# untitled.net
KiCad netlist of a schematic drawn in EAGLE
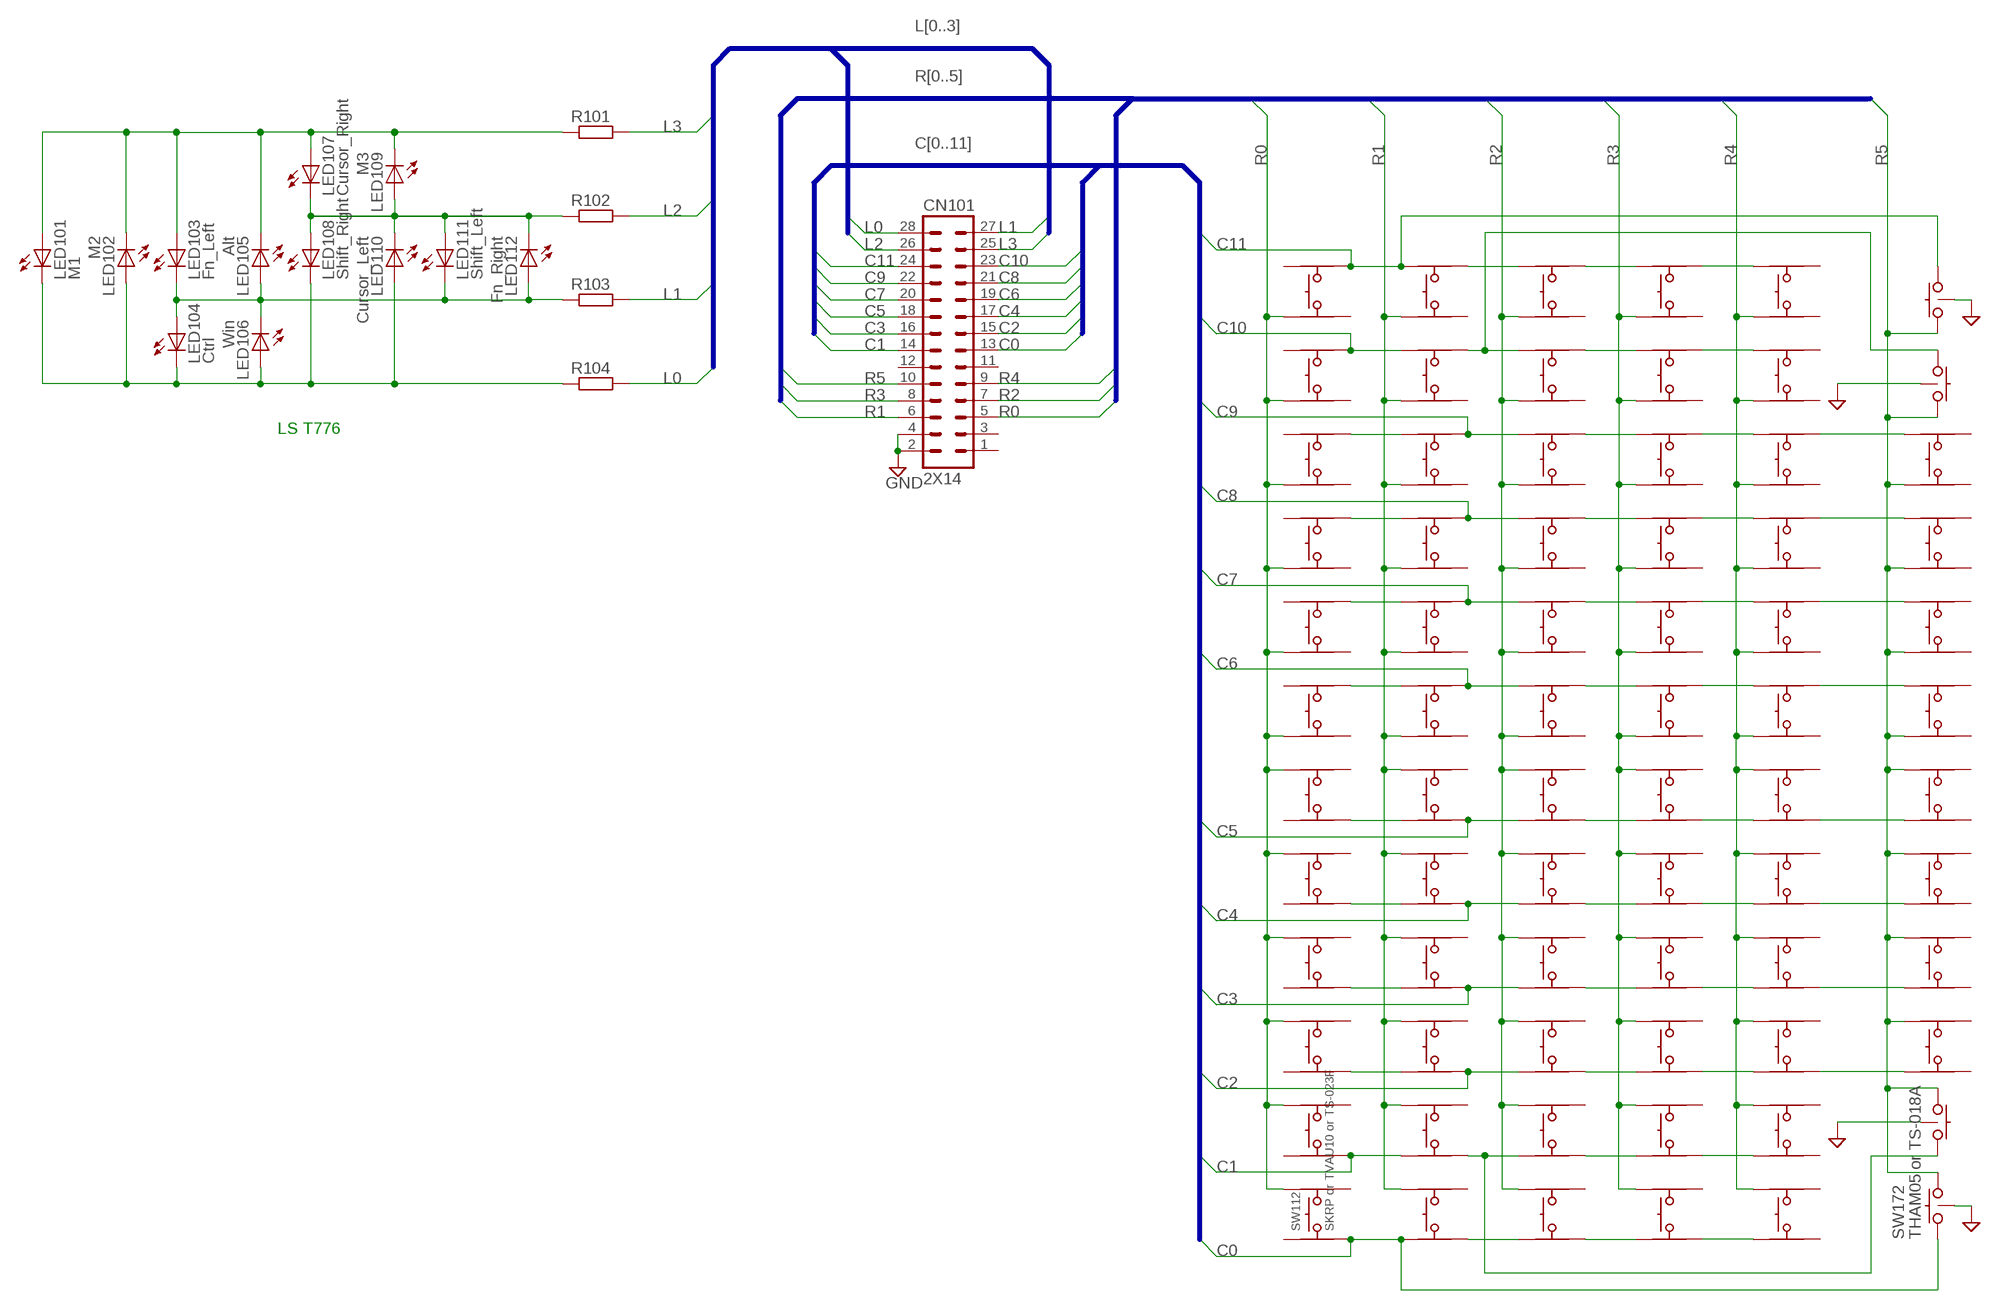
[diagram p0: schematic, sheet 1]

(export (version "E")
  (design (tool "Eeschema 10.0.6"))
  (components
    (comp (ref "CN101")
      (value "2X14")
      (footprint "eagle-import:2MM_14X2")
      (libsource (lib "eagle-import") (part "2X14"))
    )
    (comp (ref "LED101")
      (value "M1")
      (footprint "eagle-import:P-LCC-2-TOPLED-RG")
      (libsource (lib "eagle-import") (part "LEDP-LCC-2-BACK"))
    )
    (comp (ref "LED102")
      (value "M2")
      (footprint "eagle-import:P-LCC-2-TOPLED-RG")
      (libsource (lib "eagle-import") (part "LEDP-LCC-2-BACK"))
    )
    (comp (ref "LED103")
      (value "Fn_Left")
      (footprint "eagle-import:P-LCC-2-TOPLED-RG")
      (libsource (lib "eagle-import") (part "LEDP-LCC-2-BACK"))
    )
    (comp (ref "LED104")
      (value "Ctrl")
      (footprint "eagle-import:P-LCC-2-TOPLED-RG")
      (libsource (lib "eagle-import") (part "LEDP-LCC-2-BACK"))
    )
    (comp (ref "LED105")
      (value "Alt")
      (footprint "eagle-import:P-LCC-2-TOPLED-RG")
      (libsource (lib "eagle-import") (part "LEDP-LCC-2-BACK"))
    )
    (comp (ref "LED106")
      (value "Win")
      (footprint "eagle-import:P-LCC-2-TOPLED-RG")
      (libsource (lib "eagle-import") (part "LEDP-LCC-2-BACK"))
    )
    (comp (ref "LED107")
      (value "Cursor_Right")
      (footprint "eagle-import:P-LCC-2-TOPLED-RG")
      (libsource (lib "eagle-import") (part "LEDP-LCC-2-BACK"))
    )
    (comp (ref "LED108")
      (value "Shift_Right")
      (footprint "eagle-import:P-LCC-2-TOPLED-RG")
      (libsource (lib "eagle-import") (part "LEDP-LCC-2-BACK"))
    )
    (comp (ref "LED109")
      (value "M3")
      (footprint "eagle-import:P-LCC-2-TOPLED-RG")
      (libsource (lib "eagle-import") (part "LEDP-LCC-2-BACK"))
    )
    (comp (ref "LED110")
      (value "Cursor_Left")
      (footprint "eagle-import:P-LCC-2-TOPLED-RG")
      (libsource (lib "eagle-import") (part "LEDP-LCC-2-BACK"))
    )
    (comp (ref "LED111")
      (value "Shift_Left")
      (footprint "eagle-import:P-LCC-2-TOPLED-RG")
      (libsource (lib "eagle-import") (part "LEDP-LCC-2-BACK"))
    )
    (comp (ref "LED112")
      (value "Fn_Right")
      (footprint "eagle-import:P-LCC-2-TOPLED-RG")
      (libsource (lib "eagle-import") (part "LEDP-LCC-2-BACK"))
    )
    (comp (ref "R101")
      (value "R-EU_R0402-SS")
      (footprint "eagle-import:R0402-SS")
      (libsource (lib "eagle-import") (part "R-EU_R0402-SS"))
    )
    (comp (ref "R102")
      (value "R-EU_R0402-SS")
      (footprint "eagle-import:R0402-SS")
      (libsource (lib "eagle-import") (part "R-EU_R0402-SS"))
    )
    (comp (ref "R103")
      (value "R-EU_R0402-SS")
      (footprint "eagle-import:R0402-SS")
      (libsource (lib "eagle-import") (part "R-EU_R0402-SS"))
    )
    (comp (ref "R104")
      (value "R-EU_R0402-SS")
      (footprint "eagle-import:R0402-SS")
      (libsource (lib "eagle-import") (part "R-EU_R0402-SS"))
    )
    (comp (ref "SW101")
      (value "SW_4PTVAU10-025")
      (footprint "eagle-import:TVAU10-025")
      (libsource (lib "eagle-import") (part "SW_4PTVAU10-025"))
    )
    (comp (ref "SW102")
      (value "SW_4PTVAU10-025")
      (footprint "eagle-import:TVAU10-025")
      (libsource (lib "eagle-import") (part "SW_4PTVAU10-025"))
    )
    (comp (ref "SW103")
      (value "SW_4PTVAU10-025")
      (footprint "eagle-import:TVAU10-025")
      (libsource (lib "eagle-import") (part "SW_4PTVAU10-025"))
    )
    (comp (ref "SW104")
      (value "SW_4PTVAU10-025")
      (footprint "eagle-import:TVAU10-025")
      (libsource (lib "eagle-import") (part "SW_4PTVAU10-025"))
    )
    (comp (ref "SW105")
      (value "SW_4PTVAU10-025")
      (footprint "eagle-import:TVAU10-025")
      (libsource (lib "eagle-import") (part "SW_4PTVAU10-025"))
    )
    (comp (ref "SW106")
      (value "SW_4PTVAU10-025")
      (footprint "eagle-import:TVAU10-025")
      (libsource (lib "eagle-import") (part "SW_4PTVAU10-025"))
    )
    (comp (ref "SW107")
      (value "SW_4PTVAU10-025")
      (footprint "eagle-import:TVAU10-025")
      (libsource (lib "eagle-import") (part "SW_4PTVAU10-025"))
    )
    (comp (ref "SW108")
      (value "SW_4PTVAU10-025")
      (footprint "eagle-import:TVAU10-025")
      (libsource (lib "eagle-import") (part "SW_4PTVAU10-025"))
    )
    (comp (ref "SW109")
      (value "SW_4PTVAU10-025")
      (footprint "eagle-import:TVAU10-025")
      (libsource (lib "eagle-import") (part "SW_4PTVAU10-025"))
    )
    (comp (ref "SW110")
      (value "SW_4PTVAU10-025")
      (footprint "eagle-import:TVAU10-025")
      (libsource (lib "eagle-import") (part "SW_4PTVAU10-025"))
    )
    (comp (ref "SW111")
      (value "SW_4PTVAU10-025")
      (footprint "eagle-import:TVAU10-025")
      (libsource (lib "eagle-import") (part "SW_4PTVAU10-025"))
    )
    (comp (ref "SW112")
      (value "SKRP or TVAU10 or TS-023F")
      (footprint "eagle-import:TVAU10-025")
      (libsource (lib "eagle-import") (part "SW_4PTVAU10-025"))
    )
    (comp (ref "SW113")
      (value "SW_4PTVAU10-025")
      (footprint "eagle-import:TVAU10-025")
      (libsource (lib "eagle-import") (part "SW_4PTVAU10-025"))
    )
    (comp (ref "SW114")
      (value "SW_4PTVAU10-025")
      (footprint "eagle-import:TVAU10-025")
      (libsource (lib "eagle-import") (part "SW_4PTVAU10-025"))
    )
    (comp (ref "SW115")
      (value "SW_4PTVAU10-025")
      (footprint "eagle-import:TVAU10-025")
      (libsource (lib "eagle-import") (part "SW_4PTVAU10-025"))
    )
    (comp (ref "SW116")
      (value "SW_4PTVAU10-025")
      (footprint "eagle-import:TVAU10-025")
      (libsource (lib "eagle-import") (part "SW_4PTVAU10-025"))
    )
    (comp (ref "SW117")
      (value "SW_4PTVAU10-025")
      (footprint "eagle-import:TVAU10-025")
      (libsource (lib "eagle-import") (part "SW_4PTVAU10-025"))
    )
    (comp (ref "SW118")
      (value "SW_4PTVAU10-025")
      (footprint "eagle-import:TVAU10-025")
      (libsource (lib "eagle-import") (part "SW_4PTVAU10-025"))
    )
    (comp (ref "SW119")
      (value "SW_4PTVAU10-025")
      (footprint "eagle-import:TVAU10-025")
      (libsource (lib "eagle-import") (part "SW_4PTVAU10-025"))
    )
    (comp (ref "SW120")
      (value "SW_4PTVAU10-025")
      (footprint "eagle-import:TVAU10-025")
      (libsource (lib "eagle-import") (part "SW_4PTVAU10-025"))
    )
    (comp (ref "SW121")
      (value "SW_4PTVAU10-025")
      (footprint "eagle-import:TVAU10-025")
      (libsource (lib "eagle-import") (part "SW_4PTVAU10-025"))
    )
    (comp (ref "SW122")
      (value "SW_4PTVAU10-025")
      (footprint "eagle-import:TVAU10-025")
      (libsource (lib "eagle-import") (part "SW_4PTVAU10-025"))
    )
    (comp (ref "SW123")
      (value "SW_4PTVAU10-025")
      (footprint "eagle-import:TVAU10-025")
      (libsource (lib "eagle-import") (part "SW_4PTVAU10-025"))
    )
    (comp (ref "SW124")
      (value "SW_4PTVAU10-025")
      (footprint "eagle-import:TVAU10-025")
      (libsource (lib "eagle-import") (part "SW_4PTVAU10-025"))
    )
    (comp (ref "SW125")
      (value "SW_4PTVAU10-025")
      (footprint "eagle-import:TVAU10-025")
      (libsource (lib "eagle-import") (part "SW_4PTVAU10-025"))
    )
    (comp (ref "SW126")
      (value "SW_4PTVAU10-025")
      (footprint "eagle-import:TVAU10-025")
      (libsource (lib "eagle-import") (part "SW_4PTVAU10-025"))
    )
    (comp (ref "SW127")
      (value "SW_4PTVAU10-025")
      (footprint "eagle-import:TVAU10-025")
      (libsource (lib "eagle-import") (part "SW_4PTVAU10-025"))
    )
    (comp (ref "SW128")
      (value "SW_4PTVAU10-025")
      (footprint "eagle-import:TVAU10-025")
      (libsource (lib "eagle-import") (part "SW_4PTVAU10-025"))
    )
    (comp (ref "SW129")
      (value "SW_4PTVAU10-025")
      (footprint "eagle-import:TVAU10-025")
      (libsource (lib "eagle-import") (part "SW_4PTVAU10-025"))
    )
    (comp (ref "SW130")
      (value "SW_4PTVAU10-025")
      (footprint "eagle-import:TVAU10-025")
      (libsource (lib "eagle-import") (part "SW_4PTVAU10-025"))
    )
    (comp (ref "SW131")
      (value "SW_4PTVAU10-025")
      (footprint "eagle-import:TVAU10-025")
      (libsource (lib "eagle-import") (part "SW_4PTVAU10-025"))
    )
    (comp (ref "SW132")
      (value "SW_4PTVAU10-025")
      (footprint "eagle-import:TVAU10-025")
      (libsource (lib "eagle-import") (part "SW_4PTVAU10-025"))
    )
    (comp (ref "SW133")
      (value "SW_4PTVAU10-025")
      (footprint "eagle-import:TVAU10-025")
      (libsource (lib "eagle-import") (part "SW_4PTVAU10-025"))
    )
    (comp (ref "SW134")
      (value "SW_4PTVAU10-025")
      (footprint "eagle-import:TVAU10-025")
      (libsource (lib "eagle-import") (part "SW_4PTVAU10-025"))
    )
    (comp (ref "SW135")
      (value "SW_4PTVAU10-025")
      (footprint "eagle-import:TVAU10-025")
      (libsource (lib "eagle-import") (part "SW_4PTVAU10-025"))
    )
    (comp (ref "SW136")
      (value "SW_4PTVAU10-025")
      (footprint "eagle-import:TVAU10-025")
      (libsource (lib "eagle-import") (part "SW_4PTVAU10-025"))
    )
    (comp (ref "SW137")
      (value "SW_4PTVAU10-025")
      (footprint "eagle-import:TVAU10-025")
      (libsource (lib "eagle-import") (part "SW_4PTVAU10-025"))
    )
    (comp (ref "SW138")
      (value "SW_4PTVAU10-025")
      (footprint "eagle-import:TVAU10-025")
      (libsource (lib "eagle-import") (part "SW_4PTVAU10-025"))
    )
    (comp (ref "SW139")
      (value "SW_4PTVAU10-025")
      (footprint "eagle-import:TVAU10-025")
      (libsource (lib "eagle-import") (part "SW_4PTVAU10-025"))
    )
    (comp (ref "SW140")
      (value "SW_4PTVAU10-025")
      (footprint "eagle-import:TVAU10-025")
      (libsource (lib "eagle-import") (part "SW_4PTVAU10-025"))
    )
    (comp (ref "SW141")
      (value "SW_4PTVAU10-025")
      (footprint "eagle-import:TVAU10-025")
      (libsource (lib "eagle-import") (part "SW_4PTVAU10-025"))
    )
    (comp (ref "SW142")
      (value "SW_4PTVAU10-025")
      (footprint "eagle-import:TVAU10-025")
      (libsource (lib "eagle-import") (part "SW_4PTVAU10-025"))
    )
    (comp (ref "SW143")
      (value "SW_4PTVAU10-025")
      (footprint "eagle-import:TVAU10-025")
      (libsource (lib "eagle-import") (part "SW_4PTVAU10-025"))
    )
    (comp (ref "SW144")
      (value "SW_4PTVAU10-025")
      (footprint "eagle-import:TVAU10-025")
      (libsource (lib "eagle-import") (part "SW_4PTVAU10-025"))
    )
    (comp (ref "SW145")
      (value "SW_4PTVAU10-025")
      (footprint "eagle-import:TVAU10-025")
      (libsource (lib "eagle-import") (part "SW_4PTVAU10-025"))
    )
    (comp (ref "SW146")
      (value "SW_4PTVAU10-025")
      (footprint "eagle-import:TVAU10-025")
      (libsource (lib "eagle-import") (part "SW_4PTVAU10-025"))
    )
    (comp (ref "SW147")
      (value "SW_4PTVAU10-025")
      (footprint "eagle-import:TVAU10-025")
      (libsource (lib "eagle-import") (part "SW_4PTVAU10-025"))
    )
    (comp (ref "SW148")
      (value "SW_4PTVAU10-025")
      (footprint "eagle-import:TVAU10-025")
      (libsource (lib "eagle-import") (part "SW_4PTVAU10-025"))
    )
    (comp (ref "SW149")
      (value "SW_4PTVAU10-025")
      (footprint "eagle-import:TVAU10-025")
      (libsource (lib "eagle-import") (part "SW_4PTVAU10-025"))
    )
    (comp (ref "SW150")
      (value "SW_4PTVAU10-025")
      (footprint "eagle-import:TVAU10-025")
      (libsource (lib "eagle-import") (part "SW_4PTVAU10-025"))
    )
    (comp (ref "SW151")
      (value "SW_4PTVAU10-025")
      (footprint "eagle-import:TVAU10-025")
      (libsource (lib "eagle-import") (part "SW_4PTVAU10-025"))
    )
    (comp (ref "SW152")
      (value "SW_4PTVAU10-025")
      (footprint "eagle-import:TVAU10-025")
      (libsource (lib "eagle-import") (part "SW_4PTVAU10-025"))
    )
    (comp (ref "SW153")
      (value "SW_4PTVAU10-025")
      (footprint "eagle-import:TVAU10-025")
      (libsource (lib "eagle-import") (part "SW_4PTVAU10-025"))
    )
    (comp (ref "SW154")
      (value "SW_4PTVAU10-025")
      (footprint "eagle-import:TVAU10-025")
      (libsource (lib "eagle-import") (part "SW_4PTVAU10-025"))
    )
    (comp (ref "SW155")
      (value "SW_4PTVAU10-025")
      (footprint "eagle-import:TVAU10-025")
      (libsource (lib "eagle-import") (part "SW_4PTVAU10-025"))
    )
    (comp (ref "SW156")
      (value "SW_4PTVAU10-025")
      (footprint "eagle-import:TVAU10-025")
      (libsource (lib "eagle-import") (part "SW_4PTVAU10-025"))
    )
    (comp (ref "SW157")
      (value "SW_4PTVAU10-025")
      (footprint "eagle-import:TVAU10-025")
      (libsource (lib "eagle-import") (part "SW_4PTVAU10-025"))
    )
    (comp (ref "SW158")
      (value "SW_4PTVAU10-025")
      (footprint "eagle-import:TVAU10-025")
      (libsource (lib "eagle-import") (part "SW_4PTVAU10-025"))
    )
    (comp (ref "SW159")
      (value "SW_4PTVAU10-025")
      (footprint "eagle-import:TVAU10-025")
      (libsource (lib "eagle-import") (part "SW_4PTVAU10-025"))
    )
    (comp (ref "SW160")
      (value "SW_4PTVAU10-025")
      (footprint "eagle-import:TVAU10-025")
      (libsource (lib "eagle-import") (part "SW_4PTVAU10-025"))
    )
    (comp (ref "SW161")
      (value "SW_WITH_EARTHX")
      (footprint "eagle-import:THAM05")
      (libsource (lib "eagle-import") (part "SW_WITH_EARTHX"))
    )
    (comp (ref "SW162")
      (value "SW_WITH_EARTHX")
      (footprint "eagle-import:THAM05")
      (libsource (lib "eagle-import") (part "SW_WITH_EARTHX"))
    )
    (comp (ref "SW163")
      (value "SW_4PTVAU10-025")
      (footprint "eagle-import:TVAU10-025")
      (libsource (lib "eagle-import") (part "SW_4PTVAU10-025"))
    )
    (comp (ref "SW164")
      (value "SW_4PTVAU10-025")
      (footprint "eagle-import:TVAU10-025")
      (libsource (lib "eagle-import") (part "SW_4PTVAU10-025"))
    )
    (comp (ref "SW165")
      (value "SW_4PTVAU10-025")
      (footprint "eagle-import:TVAU10-025")
      (libsource (lib "eagle-import") (part "SW_4PTVAU10-025"))
    )
    (comp (ref "SW166")
      (value "SW_4PTVAU10-025")
      (footprint "eagle-import:TVAU10-025")
      (libsource (lib "eagle-import") (part "SW_4PTVAU10-025"))
    )
    (comp (ref "SW167")
      (value "SW_4PTVAU10-025")
      (footprint "eagle-import:TVAU10-025")
      (libsource (lib "eagle-import") (part "SW_4PTVAU10-025"))
    )
    (comp (ref "SW168")
      (value "SW_4PTVAU10-025")
      (footprint "eagle-import:TVAU10-025")
      (libsource (lib "eagle-import") (part "SW_4PTVAU10-025"))
    )
    (comp (ref "SW169")
      (value "SW_4PTVAU10-025")
      (footprint "eagle-import:TVAU10-025")
      (libsource (lib "eagle-import") (part "SW_4PTVAU10-025"))
    )
    (comp (ref "SW170")
      (value "SW_4PTVAU10-025")
      (footprint "eagle-import:TVAU10-025")
      (libsource (lib "eagle-import") (part "SW_4PTVAU10-025"))
    )
    (comp (ref "SW171")
      (value "SW_WITH_EARTHX")
      (footprint "eagle-import:THAM05")
      (libsource (lib "eagle-import") (part "SW_WITH_EARTHX"))
    )
    (comp (ref "SW172")
      (value "THAM05 or TS-018A")
      (footprint "eagle-import:THAM05")
      (libsource (lib "eagle-import") (part "SW_WITH_EARTHX"))
    )
  )
  (nets
    (net (code "1") (name "/C0") (class "Default")
      (node (ref "CN101") (pin "13") (pinfunction "13_13") (pintype "passive"))
      (node (ref "SW112") (pin "P$2") (pinfunction "=A_P$2") (pintype "bidirectional"))
      (node (ref "SW124") (pin "P$1") (pinfunction "A_P$1") (pintype "bidirectional"))
      (node (ref "SW172") (pin "P$1") (pinfunction "P$1_P$1") (pintype "passive"))
    )
    (net (code "2") (name "/C1") (class "Default")
      (node (ref "CN101") (pin "14") (pinfunction "14_14") (pintype "passive"))
      (node (ref "SW111") (pin "P$2") (pinfunction "=A_P$2") (pintype "bidirectional"))
      (node (ref "SW123") (pin "P$1") (pinfunction "A_P$1") (pintype "bidirectional"))
    )
    (net (code "3") (name "/C2") (class "Default")
      (node (ref "CN101") (pin "15") (pinfunction "15_15") (pintype "passive"))
      (node (ref "SW122") (pin "P$2") (pinfunction "=A_P$2") (pintype "bidirectional"))
      (node (ref "SW134") (pin "P$1") (pinfunction "A_P$1") (pintype "bidirectional"))
    )
    (net (code "4") (name "/C3") (class "Default")
      (node (ref "CN101") (pin "16") (pinfunction "16_16") (pintype "passive"))
      (node (ref "SW121") (pin "P$2") (pinfunction "=A_P$2") (pintype "bidirectional"))
      (node (ref "SW133") (pin "P$1") (pinfunction "A_P$1") (pintype "bidirectional"))
    )
    (net (code "5") (name "/C4") (class "Default")
      (node (ref "CN101") (pin "17") (pinfunction "17_17") (pintype "passive"))
      (node (ref "SW120") (pin "P$2") (pinfunction "=A_P$2") (pintype "bidirectional"))
      (node (ref "SW132") (pin "P$1") (pinfunction "A_P$1") (pintype "bidirectional"))
    )
    (net (code "6") (name "/C5") (class "Default")
      (node (ref "CN101") (pin "18") (pinfunction "18_18") (pintype "passive"))
      (node (ref "SW119") (pin "P$2") (pinfunction "=A_P$2") (pintype "bidirectional"))
      (node (ref "SW131") (pin "P$1") (pinfunction "A_P$1") (pintype "bidirectional"))
    )
    (net (code "7") (name "/C6") (class "Default")
      (node (ref "CN101") (pin "19") (pinfunction "19_19") (pintype "passive"))
      (node (ref "SW118") (pin "P$4") (pinfunction "=B_P$4") (pintype "bidirectional"))
      (node (ref "SW130") (pin "P$3") (pinfunction "B_P$3") (pintype "bidirectional"))
    )
    (net (code "8") (name "/C7") (class "Default")
      (node (ref "CN101") (pin "20") (pinfunction "20_20") (pintype "passive"))
      (node (ref "SW117") (pin "P$4") (pinfunction "=B_P$4") (pintype "bidirectional"))
      (node (ref "SW129") (pin "P$3") (pinfunction "B_P$3") (pintype "bidirectional"))
    )
    (net (code "9") (name "/C8") (class "Default")
      (node (ref "CN101") (pin "21") (pinfunction "21_21") (pintype "passive"))
      (node (ref "SW116") (pin "P$4") (pinfunction "=B_P$4") (pintype "bidirectional"))
      (node (ref "SW128") (pin "P$3") (pinfunction "B_P$3") (pintype "bidirectional"))
    )
    (net (code "10") (name "/C9") (class "Default")
      (node (ref "CN101") (pin "22") (pinfunction "22_22") (pintype "passive"))
      (node (ref "SW115") (pin "P$4") (pinfunction "=B_P$4") (pintype "bidirectional"))
      (node (ref "SW127") (pin "P$3") (pinfunction "B_P$3") (pintype "bidirectional"))
    )
    (net (code "11") (name "/C10") (class "Default")
      (node (ref "CN101") (pin "23") (pinfunction "23_23") (pintype "passive"))
      (node (ref "SW102") (pin "P$4") (pinfunction "=B_P$4") (pintype "bidirectional"))
      (node (ref "SW114") (pin "P$3") (pinfunction "B_P$3") (pintype "bidirectional"))
    )
    (net (code "12") (name "/C11") (class "Default")
      (node (ref "CN101") (pin "24") (pinfunction "24_24") (pintype "passive"))
      (node (ref "SW101") (pin "P$4") (pinfunction "=B_P$4") (pintype "bidirectional"))
      (node (ref "SW113") (pin "P$3") (pinfunction "B_P$3") (pintype "bidirectional"))
      (node (ref "SW161") (pin "P$2") (pinfunction "P$2_P$2") (pintype "passive"))
    )
    (net (code "14") (name "/L0") (class "Default")
      (node (ref "CN101") (pin "28") (pinfunction "28_28") (pintype "passive"))
      (node (ref "R104") (pin "2") (pinfunction "2_2") (pintype "passive"))
    )
    (net (code "15") (name "/L1") (class "Default")
      (node (ref "CN101") (pin "27") (pinfunction "27_27") (pintype "passive"))
      (node (ref "R103") (pin "2") (pinfunction "2_2") (pintype "passive"))
    )
    (net (code "16") (name "/L2") (class "Default")
      (node (ref "CN101") (pin "26") (pinfunction "26_26") (pintype "passive"))
      (node (ref "R102") (pin "2") (pinfunction "2_2") (pintype "passive"))
    )
    (net (code "17") (name "/L3") (class "Default")
      (node (ref "CN101") (pin "25") (pinfunction "25_25") (pintype "passive"))
      (node (ref "R101") (pin "2") (pinfunction "2_2") (pintype "passive"))
    )
    (net (code "19") (name "/R0") (class "Default")
      (node (ref "CN101") (pin "5") (pinfunction "5_5") (pintype "passive"))
      (node (ref "SW101") (pin "P$1") (pinfunction "A_P$1") (pintype "bidirectional"))
      (node (ref "SW102") (pin "P$1") (pinfunction "A_P$1") (pintype "bidirectional"))
      (node (ref "SW103") (pin "P$1") (pinfunction "A_P$1") (pintype "bidirectional"))
      (node (ref "SW104") (pin "P$1") (pinfunction "A_P$1") (pintype "bidirectional"))
      (node (ref "SW105") (pin "P$1") (pinfunction "A_P$1") (pintype "bidirectional"))
      (node (ref "SW106") (pin "P$1") (pinfunction "A_P$1") (pintype "bidirectional"))
      (node (ref "SW107") (pin "P$3") (pinfunction "B_P$3") (pintype "bidirectional"))
      (node (ref "SW108") (pin "P$3") (pinfunction "B_P$3") (pintype "bidirectional"))
      (node (ref "SW109") (pin "P$3") (pinfunction "B_P$3") (pintype "bidirectional"))
      (node (ref "SW110") (pin "P$3") (pinfunction "B_P$3") (pintype "bidirectional"))
      (node (ref "SW111") (pin "P$3") (pinfunction "B_P$3") (pintype "bidirectional"))
      (node (ref "SW112") (pin "P$3") (pinfunction "B_P$3") (pintype "bidirectional"))
    )
    (net (code "20") (name "/R1") (class "Default")
      (node (ref "CN101") (pin "6") (pinfunction "6_6") (pintype "passive"))
      (node (ref "SW113") (pin "P$1") (pinfunction "A_P$1") (pintype "bidirectional"))
      (node (ref "SW114") (pin "P$1") (pinfunction "A_P$1") (pintype "bidirectional"))
      (node (ref "SW115") (pin "P$1") (pinfunction "A_P$1") (pintype "bidirectional"))
      (node (ref "SW116") (pin "P$1") (pinfunction "A_P$1") (pintype "bidirectional"))
      (node (ref "SW117") (pin "P$1") (pinfunction "A_P$1") (pintype "bidirectional"))
      (node (ref "SW118") (pin "P$1") (pinfunction "A_P$1") (pintype "bidirectional"))
      (node (ref "SW119") (pin "P$3") (pinfunction "B_P$3") (pintype "bidirectional"))
      (node (ref "SW120") (pin "P$3") (pinfunction "B_P$3") (pintype "bidirectional"))
      (node (ref "SW121") (pin "P$3") (pinfunction "B_P$3") (pintype "bidirectional"))
      (node (ref "SW122") (pin "P$3") (pinfunction "B_P$3") (pintype "bidirectional"))
      (node (ref "SW123") (pin "P$3") (pinfunction "B_P$3") (pintype "bidirectional"))
      (node (ref "SW124") (pin "P$3") (pinfunction "B_P$3") (pintype "bidirectional"))
    )
    (net (code "21") (name "/R2") (class "Default")
      (node (ref "CN101") (pin "7") (pinfunction "7_7") (pintype "passive"))
      (node (ref "SW125") (pin "P$1") (pinfunction "A_P$1") (pintype "bidirectional"))
      (node (ref "SW126") (pin "P$1") (pinfunction "A_P$1") (pintype "bidirectional"))
      (node (ref "SW127") (pin "P$1") (pinfunction "A_P$1") (pintype "bidirectional"))
      (node (ref "SW128") (pin "P$1") (pinfunction "A_P$1") (pintype "bidirectional"))
      (node (ref "SW129") (pin "P$1") (pinfunction "A_P$1") (pintype "bidirectional"))
      (node (ref "SW130") (pin "P$1") (pinfunction "A_P$1") (pintype "bidirectional"))
      (node (ref "SW131") (pin "P$3") (pinfunction "B_P$3") (pintype "bidirectional"))
      (node (ref "SW132") (pin "P$3") (pinfunction "B_P$3") (pintype "bidirectional"))
      (node (ref "SW133") (pin "P$3") (pinfunction "B_P$3") (pintype "bidirectional"))
      (node (ref "SW134") (pin "P$3") (pinfunction "B_P$3") (pintype "bidirectional"))
      (node (ref "SW135") (pin "P$3") (pinfunction "B_P$3") (pintype "bidirectional"))
      (node (ref "SW136") (pin "P$3") (pinfunction "B_P$3") (pintype "bidirectional"))
    )
    (net (code "22") (name "/R3") (class "Default")
      (node (ref "CN101") (pin "8") (pinfunction "8_8") (pintype "passive"))
      (node (ref "SW137") (pin "P$1") (pinfunction "A_P$1") (pintype "bidirectional"))
      (node (ref "SW138") (pin "P$1") (pinfunction "A_P$1") (pintype "bidirectional"))
      (node (ref "SW139") (pin "P$1") (pinfunction "A_P$1") (pintype "bidirectional"))
      (node (ref "SW140") (pin "P$1") (pinfunction "A_P$1") (pintype "bidirectional"))
      (node (ref "SW141") (pin "P$1") (pinfunction "A_P$1") (pintype "bidirectional"))
      (node (ref "SW142") (pin "P$1") (pinfunction "A_P$1") (pintype "bidirectional"))
      (node (ref "SW143") (pin "P$3") (pinfunction "B_P$3") (pintype "bidirectional"))
      (node (ref "SW144") (pin "P$3") (pinfunction "B_P$3") (pintype "bidirectional"))
      (node (ref "SW145") (pin "P$3") (pinfunction "B_P$3") (pintype "bidirectional"))
      (node (ref "SW146") (pin "P$3") (pinfunction "B_P$3") (pintype "bidirectional"))
      (node (ref "SW147") (pin "P$3") (pinfunction "B_P$3") (pintype "bidirectional"))
      (node (ref "SW148") (pin "P$3") (pinfunction "B_P$3") (pintype "bidirectional"))
    )
    (net (code "23") (name "/R4") (class "Default")
      (node (ref "CN101") (pin "9") (pinfunction "9_9") (pintype "passive"))
      (node (ref "SW149") (pin "P$1") (pinfunction "A_P$1") (pintype "bidirectional"))
      (node (ref "SW150") (pin "P$1") (pinfunction "A_P$1") (pintype "bidirectional"))
      (node (ref "SW151") (pin "P$1") (pinfunction "A_P$1") (pintype "bidirectional"))
      (node (ref "SW152") (pin "P$1") (pinfunction "A_P$1") (pintype "bidirectional"))
      (node (ref "SW153") (pin "P$1") (pinfunction "A_P$1") (pintype "bidirectional"))
      (node (ref "SW154") (pin "P$1") (pinfunction "A_P$1") (pintype "bidirectional"))
      (node (ref "SW155") (pin "P$3") (pinfunction "B_P$3") (pintype "bidirectional"))
      (node (ref "SW156") (pin "P$3") (pinfunction "B_P$3") (pintype "bidirectional"))
      (node (ref "SW157") (pin "P$3") (pinfunction "B_P$3") (pintype "bidirectional"))
      (node (ref "SW158") (pin "P$3") (pinfunction "B_P$3") (pintype "bidirectional"))
      (node (ref "SW159") (pin "P$3") (pinfunction "B_P$3") (pintype "bidirectional"))
      (node (ref "SW160") (pin "P$3") (pinfunction "B_P$3") (pintype "bidirectional"))
    )
    (net (code "24") (name "/R5") (class "Default")
      (node (ref "CN101") (pin "10") (pinfunction "10_10") (pintype "passive"))
      (node (ref "SW161") (pin "P$1") (pinfunction "P$1_P$1") (pintype "passive"))
      (node (ref "SW162") (pin "P$2") (pinfunction "P$2_P$2") (pintype "passive"))
      (node (ref "SW163") (pin "P$1") (pinfunction "A_P$1") (pintype "bidirectional"))
      (node (ref "SW164") (pin "P$1") (pinfunction "A_P$1") (pintype "bidirectional"))
      (node (ref "SW165") (pin "P$1") (pinfunction "A_P$1") (pintype "bidirectional"))
      (node (ref "SW166") (pin "P$1") (pinfunction "A_P$1") (pintype "bidirectional"))
      (node (ref "SW167") (pin "P$3") (pinfunction "B_P$3") (pintype "bidirectional"))
      (node (ref "SW168") (pin "P$3") (pinfunction "B_P$3") (pintype "bidirectional"))
      (node (ref "SW169") (pin "P$3") (pinfunction "B_P$3") (pintype "bidirectional"))
      (node (ref "SW170") (pin "P$3") (pinfunction "B_P$3") (pintype "bidirectional"))
      (node (ref "SW171") (pin "P$1") (pinfunction "P$1_P$1") (pintype "passive"))
      (node (ref "SW172") (pin "P$2") (pinfunction "P$2_P$2") (pintype "passive"))
    )
    (net (code "26") (name "GND") (class "Default")
      (node (ref "CN101") (pin "2") (pinfunction "2_2") (pintype "passive"))
      (node (ref "CN101") (pin "4") (pinfunction "4_4") (pintype "passive"))
      (node (ref "SW161") (pin "S1") (pinfunction "P$3_S1") (pintype "passive"))
      (node (ref "SW161") (pin "S2") (pinfunction "P$3_S2") (pintype "passive"))
      (node (ref "SW161") (pin "S3") (pinfunction "P$3_S3") (pintype "passive"))
      (node (ref "SW161") (pin "S4") (pinfunction "P$3_S4") (pintype "passive"))
      (node (ref "SW161") (pin "S5") (pinfunction "P$3_S5") (pintype "passive"))
      (node (ref "SW162") (pin "S1") (pinfunction "P$3_S1") (pintype "passive"))
      (node (ref "SW162") (pin "S2") (pinfunction "P$3_S2") (pintype "passive"))
      (node (ref "SW162") (pin "S3") (pinfunction "P$3_S3") (pintype "passive"))
      (node (ref "SW162") (pin "S4") (pinfunction "P$3_S4") (pintype "passive"))
      (node (ref "SW162") (pin "S5") (pinfunction "P$3_S5") (pintype "passive"))
      (node (ref "SW171") (pin "S1") (pinfunction "P$3_S1") (pintype "passive"))
      (node (ref "SW171") (pin "S2") (pinfunction "P$3_S2") (pintype "passive"))
      (node (ref "SW171") (pin "S3") (pinfunction "P$3_S3") (pintype "passive"))
      (node (ref "SW171") (pin "S4") (pinfunction "P$3_S4") (pintype "passive"))
      (node (ref "SW171") (pin "S5") (pinfunction "P$3_S5") (pintype "passive"))
      (node (ref "SW172") (pin "S1") (pinfunction "P$3_S1") (pintype "passive"))
      (node (ref "SW172") (pin "S2") (pinfunction "P$3_S2") (pintype "passive"))
      (node (ref "SW172") (pin "S3") (pinfunction "P$3_S3") (pintype "passive"))
      (node (ref "SW172") (pin "S4") (pinfunction "P$3_S4") (pintype "passive"))
      (node (ref "SW172") (pin "S5") (pinfunction "P$3_S5") (pintype "passive"))
    )
    (net (code "27") (name "Net-(LED101-PadA)") (class "Default")
      (node (ref "LED101") (pin "A") (pinfunction "A_A") (pintype "passive"))
      (node (ref "LED102") (pin "C") (pinfunction "C_C") (pintype "passive"))
      (node (ref "LED103") (pin "A") (pinfunction "A_A") (pintype "passive"))
      (node (ref "LED105") (pin "C") (pinfunction "C_C") (pintype "passive"))
      (node (ref "LED107") (pin "A") (pinfunction "A_A") (pintype "passive"))
      (node (ref "LED109") (pin "C") (pinfunction "C_C") (pintype "passive"))
      (node (ref "R101") (pin "1") (pinfunction "1_1") (pintype "passive"))
    )
    (net (code "28") (name "Net-(LED101-PadC)") (class "Default")
      (node (ref "LED101") (pin "C") (pinfunction "C_C") (pintype "passive"))
      (node (ref "LED102") (pin "A") (pinfunction "A_A") (pintype "passive"))
      (node (ref "LED104") (pin "C") (pinfunction "C_C") (pintype "passive"))
      (node (ref "LED106") (pin "A") (pinfunction "A_A") (pintype "passive"))
      (node (ref "LED108") (pin "C") (pinfunction "C_C") (pintype "passive"))
      (node (ref "LED110") (pin "A") (pinfunction "A_A") (pintype "passive"))
      (node (ref "R104") (pin "1") (pinfunction "1_1") (pintype "passive"))
    )
    (net (code "29") (name "Net-(LED103-PadC)") (class "Default")
      (node (ref "LED103") (pin "C") (pinfunction "C_C") (pintype "passive"))
      (node (ref "LED104") (pin "A") (pinfunction "A_A") (pintype "passive"))
      (node (ref "LED105") (pin "A") (pinfunction "A_A") (pintype "passive"))
      (node (ref "LED106") (pin "C") (pinfunction "C_C") (pintype "passive"))
      (node (ref "LED111") (pin "C") (pinfunction "C_C") (pintype "passive"))
      (node (ref "LED112") (pin "A") (pinfunction "A_A") (pintype "passive"))
      (node (ref "R103") (pin "1") (pinfunction "1_1") (pintype "passive"))
    )
    (net (code "30") (name "Net-(LED107-PadC)") (class "Default")
      (node (ref "LED107") (pin "C") (pinfunction "C_C") (pintype "passive"))
      (node (ref "LED108") (pin "A") (pinfunction "A_A") (pintype "passive"))
      (node (ref "LED109") (pin "A") (pinfunction "A_A") (pintype "passive"))
      (node (ref "LED110") (pin "C") (pinfunction "C_C") (pintype "passive"))
      (node (ref "LED111") (pin "A") (pinfunction "A_A") (pintype "passive"))
      (node (ref "LED112") (pin "C") (pinfunction "C_C") (pintype "passive"))
      (node (ref "R102") (pin "1") (pinfunction "1_1") (pintype "passive"))
    )
    (net (code "31") (name "Net-(SW103-=B)") (class "Default")
      (node (ref "SW103") (pin "P$4") (pinfunction "=B_P$4") (pintype "bidirectional"))
      (node (ref "SW115") (pin "P$3") (pinfunction "B_P$3") (pintype "bidirectional"))
    )
    (net (code "32") (name "Net-(SW104-=B)") (class "Default")
      (node (ref "SW104") (pin "P$4") (pinfunction "=B_P$4") (pintype "bidirectional"))
      (node (ref "SW116") (pin "P$3") (pinfunction "B_P$3") (pintype "bidirectional"))
    )
    (net (code "33") (name "Net-(SW105-=B)") (class "Default")
      (node (ref "SW105") (pin "P$4") (pinfunction "=B_P$4") (pintype "bidirectional"))
      (node (ref "SW117") (pin "P$3") (pinfunction "B_P$3") (pintype "bidirectional"))
    )
    (net (code "34") (name "Net-(SW106-=B)") (class "Default")
      (node (ref "SW106") (pin "P$4") (pinfunction "=B_P$4") (pintype "bidirectional"))
      (node (ref "SW118") (pin "P$3") (pinfunction "B_P$3") (pintype "bidirectional"))
    )
    (net (code "35") (name "Net-(SW107-=A)") (class "Default")
      (node (ref "SW107") (pin "P$2") (pinfunction "=A_P$2") (pintype "bidirectional"))
      (node (ref "SW119") (pin "P$1") (pinfunction "A_P$1") (pintype "bidirectional"))
    )
    (net (code "36") (name "Net-(SW108-=A)") (class "Default")
      (node (ref "SW108") (pin "P$2") (pinfunction "=A_P$2") (pintype "bidirectional"))
      (node (ref "SW120") (pin "P$1") (pinfunction "A_P$1") (pintype "bidirectional"))
    )
    (net (code "37") (name "Net-(SW109-=A)") (class "Default")
      (node (ref "SW109") (pin "P$2") (pinfunction "=A_P$2") (pintype "bidirectional"))
      (node (ref "SW121") (pin "P$1") (pinfunction "A_P$1") (pintype "bidirectional"))
    )
    (net (code "38") (name "Net-(SW110-=A)") (class "Default")
      (node (ref "SW110") (pin "P$2") (pinfunction "=A_P$2") (pintype "bidirectional"))
      (node (ref "SW122") (pin "P$1") (pinfunction "A_P$1") (pintype "bidirectional"))
    )
    (net (code "39") (name "Net-(SW113-=B)") (class "Default")
      (node (ref "SW113") (pin "P$4") (pinfunction "=B_P$4") (pintype "bidirectional"))
      (node (ref "SW125") (pin "P$3") (pinfunction "B_P$3") (pintype "bidirectional"))
    )
    (net (code "40") (name "Net-(SW114-=B)") (class "Default")
      (node (ref "SW114") (pin "P$4") (pinfunction "=B_P$4") (pintype "bidirectional"))
      (node (ref "SW126") (pin "P$3") (pinfunction "B_P$3") (pintype "bidirectional"))
      (node (ref "SW162") (pin "P$1") (pinfunction "P$1_P$1") (pintype "passive"))
    )
    (net (code "41") (name "Net-(SW123-=A)") (class "Default")
      (node (ref "SW123") (pin "P$2") (pinfunction "=A_P$2") (pintype "bidirectional"))
      (node (ref "SW135") (pin "P$1") (pinfunction "A_P$1") (pintype "bidirectional"))
      (node (ref "SW171") (pin "P$2") (pinfunction "P$2_P$2") (pintype "passive"))
    )
    (net (code "42") (name "Net-(SW124-=A)") (class "Default")
      (node (ref "SW124") (pin "P$2") (pinfunction "=A_P$2") (pintype "bidirectional"))
      (node (ref "SW136") (pin "P$1") (pinfunction "A_P$1") (pintype "bidirectional"))
    )
    (net (code "43") (name "Net-(SW125-=B)") (class "Default")
      (node (ref "SW125") (pin "P$4") (pinfunction "=B_P$4") (pintype "bidirectional"))
      (node (ref "SW137") (pin "P$3") (pinfunction "B_P$3") (pintype "bidirectional"))
    )
    (net (code "44") (name "Net-(SW126-=B)") (class "Default")
      (node (ref "SW126") (pin "P$4") (pinfunction "=B_P$4") (pintype "bidirectional"))
      (node (ref "SW138") (pin "P$3") (pinfunction "B_P$3") (pintype "bidirectional"))
    )
    (net (code "45") (name "Net-(SW127-=B)") (class "Default")
      (node (ref "SW127") (pin "P$4") (pinfunction "=B_P$4") (pintype "bidirectional"))
      (node (ref "SW139") (pin "P$3") (pinfunction "B_P$3") (pintype "bidirectional"))
    )
    (net (code "46") (name "Net-(SW128-=B)") (class "Default")
      (node (ref "SW128") (pin "P$4") (pinfunction "=B_P$4") (pintype "bidirectional"))
      (node (ref "SW140") (pin "P$3") (pinfunction "B_P$3") (pintype "bidirectional"))
    )
    (net (code "47") (name "Net-(SW129-=B)") (class "Default")
      (node (ref "SW129") (pin "P$4") (pinfunction "=B_P$4") (pintype "bidirectional"))
      (node (ref "SW141") (pin "P$3") (pinfunction "B_P$3") (pintype "bidirectional"))
    )
    (net (code "48") (name "Net-(SW130-=B)") (class "Default")
      (node (ref "SW130") (pin "P$4") (pinfunction "=B_P$4") (pintype "bidirectional"))
      (node (ref "SW142") (pin "P$3") (pinfunction "B_P$3") (pintype "bidirectional"))
    )
    (net (code "49") (name "Net-(SW131-=A)") (class "Default")
      (node (ref "SW131") (pin "P$2") (pinfunction "=A_P$2") (pintype "bidirectional"))
      (node (ref "SW143") (pin "P$1") (pinfunction "A_P$1") (pintype "bidirectional"))
    )
    (net (code "50") (name "Net-(SW132-=A)") (class "Default")
      (node (ref "SW132") (pin "P$2") (pinfunction "=A_P$2") (pintype "bidirectional"))
      (node (ref "SW144") (pin "P$1") (pinfunction "A_P$1") (pintype "bidirectional"))
    )
    (net (code "51") (name "Net-(SW133-=A)") (class "Default")
      (node (ref "SW133") (pin "P$2") (pinfunction "=A_P$2") (pintype "bidirectional"))
      (node (ref "SW145") (pin "P$1") (pinfunction "A_P$1") (pintype "bidirectional"))
    )
    (net (code "52") (name "Net-(SW134-=A)") (class "Default")
      (node (ref "SW134") (pin "P$2") (pinfunction "=A_P$2") (pintype "bidirectional"))
      (node (ref "SW146") (pin "P$1") (pinfunction "A_P$1") (pintype "bidirectional"))
    )
    (net (code "53") (name "Net-(SW135-=A)") (class "Default")
      (node (ref "SW135") (pin "P$2") (pinfunction "=A_P$2") (pintype "bidirectional"))
      (node (ref "SW147") (pin "P$1") (pinfunction "A_P$1") (pintype "bidirectional"))
    )
    (net (code "54") (name "Net-(SW136-=A)") (class "Default")
      (node (ref "SW136") (pin "P$2") (pinfunction "=A_P$2") (pintype "bidirectional"))
      (node (ref "SW148") (pin "P$1") (pinfunction "A_P$1") (pintype "bidirectional"))
    )
    (net (code "55") (name "Net-(SW137-=B)") (class "Default")
      (node (ref "SW137") (pin "P$4") (pinfunction "=B_P$4") (pintype "bidirectional"))
      (node (ref "SW149") (pin "P$3") (pinfunction "B_P$3") (pintype "bidirectional"))
    )
    (net (code "56") (name "Net-(SW138-=B)") (class "Default")
      (node (ref "SW138") (pin "P$4") (pinfunction "=B_P$4") (pintype "bidirectional"))
      (node (ref "SW150") (pin "P$3") (pinfunction "B_P$3") (pintype "bidirectional"))
    )
    (net (code "57") (name "Net-(SW139-=B)") (class "Default")
      (node (ref "SW139") (pin "P$4") (pinfunction "=B_P$4") (pintype "bidirectional"))
      (node (ref "SW151") (pin "P$3") (pinfunction "B_P$3") (pintype "bidirectional"))
    )
    (net (code "58") (name "Net-(SW140-=B)") (class "Default")
      (node (ref "SW140") (pin "P$4") (pinfunction "=B_P$4") (pintype "bidirectional"))
      (node (ref "SW152") (pin "P$3") (pinfunction "B_P$3") (pintype "bidirectional"))
    )
    (net (code "59") (name "Net-(SW141-=B)") (class "Default")
      (node (ref "SW141") (pin "P$4") (pinfunction "=B_P$4") (pintype "bidirectional"))
      (node (ref "SW153") (pin "P$3") (pinfunction "B_P$3") (pintype "bidirectional"))
    )
    (net (code "60") (name "Net-(SW142-=B)") (class "Default")
      (node (ref "SW142") (pin "P$4") (pinfunction "=B_P$4") (pintype "bidirectional"))
      (node (ref "SW154") (pin "P$3") (pinfunction "B_P$3") (pintype "bidirectional"))
    )
    (net (code "61") (name "Net-(SW143-=A)") (class "Default")
      (node (ref "SW143") (pin "P$2") (pinfunction "=A_P$2") (pintype "bidirectional"))
      (node (ref "SW155") (pin "P$1") (pinfunction "A_P$1") (pintype "bidirectional"))
    )
    (net (code "62") (name "Net-(SW144-=A)") (class "Default")
      (node (ref "SW144") (pin "P$2") (pinfunction "=A_P$2") (pintype "bidirectional"))
      (node (ref "SW156") (pin "P$1") (pinfunction "A_P$1") (pintype "bidirectional"))
    )
    (net (code "63") (name "Net-(SW145-=A)") (class "Default")
      (node (ref "SW145") (pin "P$2") (pinfunction "=A_P$2") (pintype "bidirectional"))
      (node (ref "SW157") (pin "P$1") (pinfunction "A_P$1") (pintype "bidirectional"))
    )
    (net (code "64") (name "Net-(SW146-=A)") (class "Default")
      (node (ref "SW146") (pin "P$2") (pinfunction "=A_P$2") (pintype "bidirectional"))
      (node (ref "SW158") (pin "P$1") (pinfunction "A_P$1") (pintype "bidirectional"))
    )
    (net (code "65") (name "Net-(SW147-=A)") (class "Default")
      (node (ref "SW147") (pin "P$2") (pinfunction "=A_P$2") (pintype "bidirectional"))
      (node (ref "SW159") (pin "P$1") (pinfunction "A_P$1") (pintype "bidirectional"))
    )
    (net (code "66") (name "Net-(SW148-=A)") (class "Default")
      (node (ref "SW148") (pin "P$2") (pinfunction "=A_P$2") (pintype "bidirectional"))
      (node (ref "SW160") (pin "P$1") (pinfunction "A_P$1") (pintype "bidirectional"))
    )
    (net (code "67") (name "Net-(SW151-=B)") (class "Default")
      (node (ref "SW151") (pin "P$4") (pinfunction "=B_P$4") (pintype "bidirectional"))
      (node (ref "SW163") (pin "P$3") (pinfunction "B_P$3") (pintype "bidirectional"))
    )
    (net (code "68") (name "Net-(SW152-=B)") (class "Default")
      (node (ref "SW152") (pin "P$4") (pinfunction "=B_P$4") (pintype "bidirectional"))
      (node (ref "SW164") (pin "P$3") (pinfunction "B_P$3") (pintype "bidirectional"))
    )
    (net (code "69") (name "Net-(SW153-=B)") (class "Default")
      (node (ref "SW153") (pin "P$4") (pinfunction "=B_P$4") (pintype "bidirectional"))
      (node (ref "SW165") (pin "P$3") (pinfunction "B_P$3") (pintype "bidirectional"))
    )
    (net (code "70") (name "Net-(SW154-=B)") (class "Default")
      (node (ref "SW154") (pin "P$4") (pinfunction "=B_P$4") (pintype "bidirectional"))
      (node (ref "SW166") (pin "P$3") (pinfunction "B_P$3") (pintype "bidirectional"))
    )
    (net (code "71") (name "Net-(SW155-=A)") (class "Default")
      (node (ref "SW155") (pin "P$2") (pinfunction "=A_P$2") (pintype "bidirectional"))
      (node (ref "SW167") (pin "P$1") (pinfunction "A_P$1") (pintype "bidirectional"))
    )
    (net (code "72") (name "Net-(SW156-=A)") (class "Default")
      (node (ref "SW156") (pin "P$2") (pinfunction "=A_P$2") (pintype "bidirectional"))
      (node (ref "SW168") (pin "P$1") (pinfunction "A_P$1") (pintype "bidirectional"))
    )
    (net (code "73") (name "Net-(SW157-=A)") (class "Default")
      (node (ref "SW157") (pin "P$2") (pinfunction "=A_P$2") (pintype "bidirectional"))
      (node (ref "SW169") (pin "P$1") (pinfunction "A_P$1") (pintype "bidirectional"))
    )
    (net (code "74") (name "Net-(SW158-=A)") (class "Default")
      (node (ref "SW158") (pin "P$2") (pinfunction "=A_P$2") (pintype "bidirectional"))
      (node (ref "SW170") (pin "P$1") (pinfunction "A_P$1") (pintype "bidirectional"))
    )
    (net (code "75") (name "unconnected-(CN101-Pad1)") (class "Default")
      (node (ref "CN101") (pin "1") (pinfunction "1_1") (pintype "passive"))
    )
    (net (code "76") (name "unconnected-(CN101-Pad3)") (class "Default")
      (node (ref "CN101") (pin "3") (pinfunction "3_3") (pintype "passive"))
    )
    (net (code "77") (name "unconnected-(CN101-Pad11)") (class "Default")
      (node (ref "CN101") (pin "11") (pinfunction "11_11") (pintype "passive"))
    )
    (net (code "78") (name "unconnected-(CN101-Pad12)") (class "Default")
      (node (ref "CN101") (pin "12") (pinfunction "12_12") (pintype "passive"))
    )
    (net (code "79") (name "unconnected-(SW101-=A-PadP$2)") (class "Default")
      (node (ref "SW101") (pin "P$2") (pinfunction "=A_P$2") (pintype "bidirectional"))
    )
    (net (code "80") (name "unconnected-(SW101-B-PadP$3)") (class "Default")
      (node (ref "SW101") (pin "P$3") (pinfunction "B_P$3") (pintype "bidirectional"))
    )
    (net (code "81") (name "unconnected-(SW102-=A-PadP$2)") (class "Default")
      (node (ref "SW102") (pin "P$2") (pinfunction "=A_P$2") (pintype "bidirectional"))
    )
    (net (code "82") (name "unconnected-(SW102-B-PadP$3)") (class "Default")
      (node (ref "SW102") (pin "P$3") (pinfunction "B_P$3") (pintype "bidirectional"))
    )
    (net (code "83") (name "unconnected-(SW103-=A-PadP$2)") (class "Default")
      (node (ref "SW103") (pin "P$2") (pinfunction "=A_P$2") (pintype "bidirectional"))
    )
    (net (code "84") (name "unconnected-(SW103-B-PadP$3)") (class "Default")
      (node (ref "SW103") (pin "P$3") (pinfunction "B_P$3") (pintype "bidirectional"))
    )
    (net (code "85") (name "unconnected-(SW104-=A-PadP$2)") (class "Default")
      (node (ref "SW104") (pin "P$2") (pinfunction "=A_P$2") (pintype "bidirectional"))
    )
    (net (code "86") (name "unconnected-(SW104-B-PadP$3)") (class "Default")
      (node (ref "SW104") (pin "P$3") (pinfunction "B_P$3") (pintype "bidirectional"))
    )
    (net (code "87") (name "unconnected-(SW105-=A-PadP$2)") (class "Default")
      (node (ref "SW105") (pin "P$2") (pinfunction "=A_P$2") (pintype "bidirectional"))
    )
    (net (code "88") (name "unconnected-(SW105-B-PadP$3)") (class "Default")
      (node (ref "SW105") (pin "P$3") (pinfunction "B_P$3") (pintype "bidirectional"))
    )
    (net (code "89") (name "unconnected-(SW106-=A-PadP$2)") (class "Default")
      (node (ref "SW106") (pin "P$2") (pinfunction "=A_P$2") (pintype "bidirectional"))
    )
    (net (code "90") (name "unconnected-(SW106-B-PadP$3)") (class "Default")
      (node (ref "SW106") (pin "P$3") (pinfunction "B_P$3") (pintype "bidirectional"))
    )
    (net (code "91") (name "unconnected-(SW107-=B-PadP$4)") (class "Default")
      (node (ref "SW107") (pin "P$4") (pinfunction "=B_P$4") (pintype "bidirectional"))
    )
    (net (code "92") (name "unconnected-(SW107-A-PadP$1)") (class "Default")
      (node (ref "SW107") (pin "P$1") (pinfunction "A_P$1") (pintype "bidirectional"))
    )
    (net (code "93") (name "unconnected-(SW108-=B-PadP$4)") (class "Default")
      (node (ref "SW108") (pin "P$4") (pinfunction "=B_P$4") (pintype "bidirectional"))
    )
    (net (code "94") (name "unconnected-(SW108-A-PadP$1)") (class "Default")
      (node (ref "SW108") (pin "P$1") (pinfunction "A_P$1") (pintype "bidirectional"))
    )
    (net (code "95") (name "unconnected-(SW109-=B-PadP$4)") (class "Default")
      (node (ref "SW109") (pin "P$4") (pinfunction "=B_P$4") (pintype "bidirectional"))
    )
    (net (code "96") (name "unconnected-(SW109-A-PadP$1)") (class "Default")
      (node (ref "SW109") (pin "P$1") (pinfunction "A_P$1") (pintype "bidirectional"))
    )
    (net (code "97") (name "unconnected-(SW110-=B-PadP$4)") (class "Default")
      (node (ref "SW110") (pin "P$4") (pinfunction "=B_P$4") (pintype "bidirectional"))
    )
    (net (code "98") (name "unconnected-(SW110-A-PadP$1)") (class "Default")
      (node (ref "SW110") (pin "P$1") (pinfunction "A_P$1") (pintype "bidirectional"))
    )
    (net (code "99") (name "unconnected-(SW111-=B-PadP$4)") (class "Default")
      (node (ref "SW111") (pin "P$4") (pinfunction "=B_P$4") (pintype "bidirectional"))
    )
    (net (code "100") (name "unconnected-(SW111-A-PadP$1)") (class "Default")
      (node (ref "SW111") (pin "P$1") (pinfunction "A_P$1") (pintype "bidirectional"))
    )
    (net (code "101") (name "unconnected-(SW112-=B-PadP$4)") (class "Default")
      (node (ref "SW112") (pin "P$4") (pinfunction "=B_P$4") (pintype "bidirectional"))
    )
    (net (code "102") (name "unconnected-(SW112-A-PadP$1)") (class "Default")
      (node (ref "SW112") (pin "P$1") (pinfunction "A_P$1") (pintype "bidirectional"))
    )
    (net (code "103") (name "unconnected-(SW113-=A-PadP$2)") (class "Default")
      (node (ref "SW113") (pin "P$2") (pinfunction "=A_P$2") (pintype "bidirectional"))
    )
    (net (code "104") (name "unconnected-(SW114-=A-PadP$2)") (class "Default")
      (node (ref "SW114") (pin "P$2") (pinfunction "=A_P$2") (pintype "bidirectional"))
    )
    (net (code "105") (name "unconnected-(SW115-=A-PadP$2)") (class "Default")
      (node (ref "SW115") (pin "P$2") (pinfunction "=A_P$2") (pintype "bidirectional"))
    )
    (net (code "106") (name "unconnected-(SW116-=A-PadP$2)") (class "Default")
      (node (ref "SW116") (pin "P$2") (pinfunction "=A_P$2") (pintype "bidirectional"))
    )
    (net (code "107") (name "unconnected-(SW117-=A-PadP$2)") (class "Default")
      (node (ref "SW117") (pin "P$2") (pinfunction "=A_P$2") (pintype "bidirectional"))
    )
    (net (code "108") (name "unconnected-(SW118-=A-PadP$2)") (class "Default")
      (node (ref "SW118") (pin "P$2") (pinfunction "=A_P$2") (pintype "bidirectional"))
    )
    (net (code "109") (name "unconnected-(SW119-=B-PadP$4)") (class "Default")
      (node (ref "SW119") (pin "P$4") (pinfunction "=B_P$4") (pintype "bidirectional"))
    )
    (net (code "110") (name "unconnected-(SW120-=B-PadP$4)") (class "Default")
      (node (ref "SW120") (pin "P$4") (pinfunction "=B_P$4") (pintype "bidirectional"))
    )
    (net (code "111") (name "unconnected-(SW121-=B-PadP$4)") (class "Default")
      (node (ref "SW121") (pin "P$4") (pinfunction "=B_P$4") (pintype "bidirectional"))
    )
    (net (code "112") (name "unconnected-(SW122-=B-PadP$4)") (class "Default")
      (node (ref "SW122") (pin "P$4") (pinfunction "=B_P$4") (pintype "bidirectional"))
    )
    (net (code "113") (name "unconnected-(SW123-=B-PadP$4)") (class "Default")
      (node (ref "SW123") (pin "P$4") (pinfunction "=B_P$4") (pintype "bidirectional"))
    )
    (net (code "114") (name "unconnected-(SW124-=B-PadP$4)") (class "Default")
      (node (ref "SW124") (pin "P$4") (pinfunction "=B_P$4") (pintype "bidirectional"))
    )
    (net (code "115") (name "unconnected-(SW125-=A-PadP$2)") (class "Default")
      (node (ref "SW125") (pin "P$2") (pinfunction "=A_P$2") (pintype "bidirectional"))
    )
    (net (code "116") (name "unconnected-(SW126-=A-PadP$2)") (class "Default")
      (node (ref "SW126") (pin "P$2") (pinfunction "=A_P$2") (pintype "bidirectional"))
    )
    (net (code "117") (name "unconnected-(SW127-=A-PadP$2)") (class "Default")
      (node (ref "SW127") (pin "P$2") (pinfunction "=A_P$2") (pintype "bidirectional"))
    )
    (net (code "118") (name "unconnected-(SW128-=A-PadP$2)") (class "Default")
      (node (ref "SW128") (pin "P$2") (pinfunction "=A_P$2") (pintype "bidirectional"))
    )
    (net (code "119") (name "unconnected-(SW129-=A-PadP$2)") (class "Default")
      (node (ref "SW129") (pin "P$2") (pinfunction "=A_P$2") (pintype "bidirectional"))
    )
    (net (code "120") (name "unconnected-(SW130-=A-PadP$2)") (class "Default")
      (node (ref "SW130") (pin "P$2") (pinfunction "=A_P$2") (pintype "bidirectional"))
    )
    (net (code "121") (name "unconnected-(SW131-=B-PadP$4)") (class "Default")
      (node (ref "SW131") (pin "P$4") (pinfunction "=B_P$4") (pintype "bidirectional"))
    )
    (net (code "122") (name "unconnected-(SW132-=B-PadP$4)") (class "Default")
      (node (ref "SW132") (pin "P$4") (pinfunction "=B_P$4") (pintype "bidirectional"))
    )
    (net (code "123") (name "unconnected-(SW133-=B-PadP$4)") (class "Default")
      (node (ref "SW133") (pin "P$4") (pinfunction "=B_P$4") (pintype "bidirectional"))
    )
    (net (code "124") (name "unconnected-(SW134-=B-PadP$4)") (class "Default")
      (node (ref "SW134") (pin "P$4") (pinfunction "=B_P$4") (pintype "bidirectional"))
    )
    (net (code "125") (name "unconnected-(SW135-=B-PadP$4)") (class "Default")
      (node (ref "SW135") (pin "P$4") (pinfunction "=B_P$4") (pintype "bidirectional"))
    )
    (net (code "126") (name "unconnected-(SW136-=B-PadP$4)") (class "Default")
      (node (ref "SW136") (pin "P$4") (pinfunction "=B_P$4") (pintype "bidirectional"))
    )
    (net (code "127") (name "unconnected-(SW137-=A-PadP$2)") (class "Default")
      (node (ref "SW137") (pin "P$2") (pinfunction "=A_P$2") (pintype "bidirectional"))
    )
    (net (code "128") (name "unconnected-(SW138-=A-PadP$2)") (class "Default")
      (node (ref "SW138") (pin "P$2") (pinfunction "=A_P$2") (pintype "bidirectional"))
    )
    (net (code "129") (name "unconnected-(SW139-=A-PadP$2)") (class "Default")
      (node (ref "SW139") (pin "P$2") (pinfunction "=A_P$2") (pintype "bidirectional"))
    )
    (net (code "130") (name "unconnected-(SW140-=A-PadP$2)") (class "Default")
      (node (ref "SW140") (pin "P$2") (pinfunction "=A_P$2") (pintype "bidirectional"))
    )
    (net (code "131") (name "unconnected-(SW141-=A-PadP$2)") (class "Default")
      (node (ref "SW141") (pin "P$2") (pinfunction "=A_P$2") (pintype "bidirectional"))
    )
    (net (code "132") (name "unconnected-(SW142-=A-PadP$2)") (class "Default")
      (node (ref "SW142") (pin "P$2") (pinfunction "=A_P$2") (pintype "bidirectional"))
    )
    (net (code "133") (name "unconnected-(SW143-=B-PadP$4)") (class "Default")
      (node (ref "SW143") (pin "P$4") (pinfunction "=B_P$4") (pintype "bidirectional"))
    )
    (net (code "134") (name "unconnected-(SW144-=B-PadP$4)") (class "Default")
      (node (ref "SW144") (pin "P$4") (pinfunction "=B_P$4") (pintype "bidirectional"))
    )
    (net (code "135") (name "unconnected-(SW145-=B-PadP$4)") (class "Default")
      (node (ref "SW145") (pin "P$4") (pinfunction "=B_P$4") (pintype "bidirectional"))
    )
    (net (code "136") (name "unconnected-(SW146-=B-PadP$4)") (class "Default")
      (node (ref "SW146") (pin "P$4") (pinfunction "=B_P$4") (pintype "bidirectional"))
    )
    (net (code "137") (name "unconnected-(SW147-=B-PadP$4)") (class "Default")
      (node (ref "SW147") (pin "P$4") (pinfunction "=B_P$4") (pintype "bidirectional"))
    )
    (net (code "138") (name "unconnected-(SW148-=B-PadP$4)") (class "Default")
      (node (ref "SW148") (pin "P$4") (pinfunction "=B_P$4") (pintype "bidirectional"))
    )
    (net (code "139") (name "unconnected-(SW149-=A-PadP$2)") (class "Default")
      (node (ref "SW149") (pin "P$2") (pinfunction "=A_P$2") (pintype "bidirectional"))
    )
    (net (code "140") (name "unconnected-(SW149-=B-PadP$4)") (class "Default")
      (node (ref "SW149") (pin "P$4") (pinfunction "=B_P$4") (pintype "bidirectional"))
    )
    (net (code "141") (name "unconnected-(SW150-=A-PadP$2)") (class "Default")
      (node (ref "SW150") (pin "P$2") (pinfunction "=A_P$2") (pintype "bidirectional"))
    )
    (net (code "142") (name "unconnected-(SW150-=B-PadP$4)") (class "Default")
      (node (ref "SW150") (pin "P$4") (pinfunction "=B_P$4") (pintype "bidirectional"))
    )
    (net (code "143") (name "unconnected-(SW151-=A-PadP$2)") (class "Default")
      (node (ref "SW151") (pin "P$2") (pinfunction "=A_P$2") (pintype "bidirectional"))
    )
    (net (code "144") (name "unconnected-(SW152-=A-PadP$2)") (class "Default")
      (node (ref "SW152") (pin "P$2") (pinfunction "=A_P$2") (pintype "bidirectional"))
    )
    (net (code "145") (name "unconnected-(SW153-=A-PadP$2)") (class "Default")
      (node (ref "SW153") (pin "P$2") (pinfunction "=A_P$2") (pintype "bidirectional"))
    )
    (net (code "146") (name "unconnected-(SW154-=A-PadP$2)") (class "Default")
      (node (ref "SW154") (pin "P$2") (pinfunction "=A_P$2") (pintype "bidirectional"))
    )
    (net (code "147") (name "unconnected-(SW155-=B-PadP$4)") (class "Default")
      (node (ref "SW155") (pin "P$4") (pinfunction "=B_P$4") (pintype "bidirectional"))
    )
    (net (code "148") (name "unconnected-(SW156-=B-PadP$4)") (class "Default")
      (node (ref "SW156") (pin "P$4") (pinfunction "=B_P$4") (pintype "bidirectional"))
    )
    (net (code "149") (name "unconnected-(SW157-=B-PadP$4)") (class "Default")
      (node (ref "SW157") (pin "P$4") (pinfunction "=B_P$4") (pintype "bidirectional"))
    )
    (net (code "150") (name "unconnected-(SW158-=B-PadP$4)") (class "Default")
      (node (ref "SW158") (pin "P$4") (pinfunction "=B_P$4") (pintype "bidirectional"))
    )
    (net (code "151") (name "unconnected-(SW159-=A-PadP$2)") (class "Default")
      (node (ref "SW159") (pin "P$2") (pinfunction "=A_P$2") (pintype "bidirectional"))
    )
    (net (code "152") (name "unconnected-(SW159-=B-PadP$4)") (class "Default")
      (node (ref "SW159") (pin "P$4") (pinfunction "=B_P$4") (pintype "bidirectional"))
    )
    (net (code "153") (name "unconnected-(SW160-=A-PadP$2)") (class "Default")
      (node (ref "SW160") (pin "P$2") (pinfunction "=A_P$2") (pintype "bidirectional"))
    )
    (net (code "154") (name "unconnected-(SW160-=B-PadP$4)") (class "Default")
      (node (ref "SW160") (pin "P$4") (pinfunction "=B_P$4") (pintype "bidirectional"))
    )
    (net (code "155") (name "unconnected-(SW163-=A-PadP$2)") (class "Default")
      (node (ref "SW163") (pin "P$2") (pinfunction "=A_P$2") (pintype "bidirectional"))
    )
    (net (code "156") (name "unconnected-(SW163-=B-PadP$4)") (class "Default")
      (node (ref "SW163") (pin "P$4") (pinfunction "=B_P$4") (pintype "bidirectional"))
    )
    (net (code "157") (name "unconnected-(SW164-=A-PadP$2)") (class "Default")
      (node (ref "SW164") (pin "P$2") (pinfunction "=A_P$2") (pintype "bidirectional"))
    )
    (net (code "158") (name "unconnected-(SW164-=B-PadP$4)") (class "Default")
      (node (ref "SW164") (pin "P$4") (pinfunction "=B_P$4") (pintype "bidirectional"))
    )
    (net (code "159") (name "unconnected-(SW165-=A-PadP$2)") (class "Default")
      (node (ref "SW165") (pin "P$2") (pinfunction "=A_P$2") (pintype "bidirectional"))
    )
    (net (code "160") (name "unconnected-(SW165-=B-PadP$4)") (class "Default")
      (node (ref "SW165") (pin "P$4") (pinfunction "=B_P$4") (pintype "bidirectional"))
    )
    (net (code "161") (name "unconnected-(SW166-=A-PadP$2)") (class "Default")
      (node (ref "SW166") (pin "P$2") (pinfunction "=A_P$2") (pintype "bidirectional"))
    )
    (net (code "162") (name "unconnected-(SW166-=B-PadP$4)") (class "Default")
      (node (ref "SW166") (pin "P$4") (pinfunction "=B_P$4") (pintype "bidirectional"))
    )
    (net (code "163") (name "unconnected-(SW167-=A-PadP$2)") (class "Default")
      (node (ref "SW167") (pin "P$2") (pinfunction "=A_P$2") (pintype "bidirectional"))
    )
    (net (code "164") (name "unconnected-(SW167-=B-PadP$4)") (class "Default")
      (node (ref "SW167") (pin "P$4") (pinfunction "=B_P$4") (pintype "bidirectional"))
    )
    (net (code "165") (name "unconnected-(SW168-=A-PadP$2)") (class "Default")
      (node (ref "SW168") (pin "P$2") (pinfunction "=A_P$2") (pintype "bidirectional"))
    )
    (net (code "166") (name "unconnected-(SW168-=B-PadP$4)") (class "Default")
      (node (ref "SW168") (pin "P$4") (pinfunction "=B_P$4") (pintype "bidirectional"))
    )
    (net (code "167") (name "unconnected-(SW169-=A-PadP$2)") (class "Default")
      (node (ref "SW169") (pin "P$2") (pinfunction "=A_P$2") (pintype "bidirectional"))
    )
    (net (code "168") (name "unconnected-(SW169-=B-PadP$4)") (class "Default")
      (node (ref "SW169") (pin "P$4") (pinfunction "=B_P$4") (pintype "bidirectional"))
    )
    (net (code "169") (name "unconnected-(SW170-=A-PadP$2)") (class "Default")
      (node (ref "SW170") (pin "P$2") (pinfunction "=A_P$2") (pintype "bidirectional"))
    )
    (net (code "170") (name "unconnected-(SW170-=B-PadP$4)") (class "Default")
      (node (ref "SW170") (pin "P$4") (pinfunction "=B_P$4") (pintype "bidirectional"))
    )
  )
)
